# STM32__nRF24GHz.net
KiCad netlist of a schematic drawn in Altium Designer
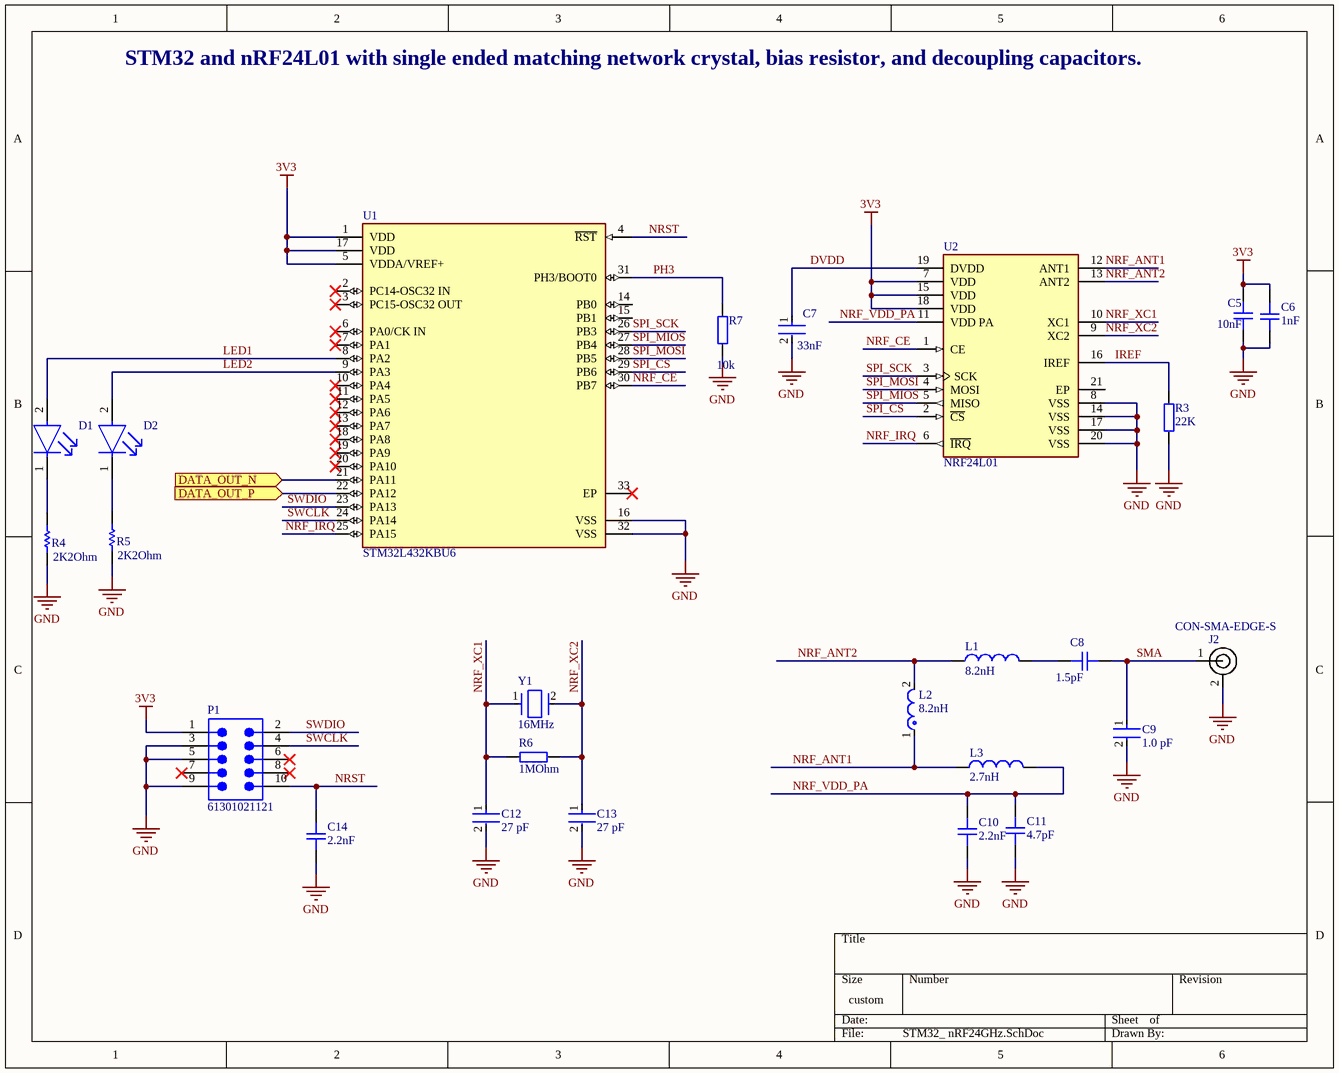
[diagram p0: STM32_ nRF24GHz.SchDoc]

(export (version "E")
  (design (tool "Eeschema 10.0.6"))
  (components
    (comp (ref "C5")
      (value "C0402")
      (footprint "CAP_0402")
      (description "Capacitor SMD 0402")
      (fields (field (name "PARAMETER 1") "10nF"))
      (libsource (lib "Schematic-Lib-PhilsLab") (part "CAP_0402"))
    )
    (comp (ref "C6")
      (value "C0402")
      (footprint "CAP_0402")
      (description "Capacitor SMD 0402")
      (fields (field (name "PARAMETER 1") "1nF"))
      (libsource (lib "Schematic-Lib-PhilsLab") (part "CAP_0402"))
    )
    (comp (ref "C7")
      (value "33nF")
      (footprint "FP-C0402-BB-MFG")
      (description "0402 C 33nF Ceramic Multilayer Capacitor; 16 V; +125degC; X7R Dielectric; +/-10%")
      (fields
        (field (name "MANUFACTURER") "Kemet")
        (field (name "MANUFACTURER PART NUMBER") "C0402C333K4RACTU")
      )
      (libsource (lib "Altium Content Vault") (part "b4654b650e69147ec39a6b967a45e02"))
    )
    (comp (ref "C8")
      (value "C0402")
      (footprint "CAP_0402")
      (description "Capacitor SMD 0402")
      (fields (field (name "PARAMETER 1") "1.5pF"))
      (libsource (lib "Schematic-Lib-PhilsLab") (part "CAP_0402"))
    )
    (comp (ref "C9")
      (value "C0402C109C5GACTU")
      (footprint "FP-C0402-BB-MFG")
      (description "CAP CER 1PF 50V NP0 0402")
      (fields
        (field (name "CAPACITANCE") "1.0 pF")
        (field (name "MANUFACTURER") "Kemet")
        (field (name "OCTOPART") "https://octopart.com/c0402c109c5gactu-kemet-9138550")
      )
      (libsource (lib "Altium Content Vault") (part "b4654b650e69147ec39a6b967a45e02"))
    )
    (comp (ref "C10")
      (value "C0402")
      (footprint "CAP_0402")
      (description "Capacitor SMD 0402")
      (fields (field (name "PARAMETER 1") "2.2nF"))
      (libsource (lib "Schematic-Lib-PhilsLab") (part "CAP_0402"))
    )
    (comp (ref "C11")
      (value "C0402")
      (footprint "CAP_0402")
      (description "Capacitor SMD 0402")
      (fields (field (name "PARAMETER 1") "4.7pF"))
      (libsource (lib "Schematic-Lib-PhilsLab") (part "CAP_0402"))
    )
    (comp (ref "C12")
      (value "27 pF")
      (footprint "FP-C0402-BB-MFG")
      (description "CAP CER 27PF 50V C0G/NP0 0402")
      (fields (field (name "MANUFACTURER") "Kemet") (field (name "TOLERANCE") "0.05"))
      (libsource (lib "Altium Content Vault") (part "b4654b650e69147ec39a6b967a45e02"))
    )
    (comp (ref "C13")
      (value "27 pF")
      (footprint "FP-C0402-BB-MFG")
      (description "CAP CER 27PF 50V C0G/NP0 0402")
      (fields (field (name "MANUFACTURER") "Kemet") (field (name "TOLERANCE") "0.05"))
      (libsource (lib "Altium Content Vault") (part "b4654b650e69147ec39a6b967a45e02"))
    )
    (comp (ref "C14")
      (value "C0402")
      (footprint "CAP_0402")
      (description "Capacitor SMD 0402")
      (fields (field (name "PARAMETER 1") "2.2nF"))
      (libsource (lib "Schematic-Lib-PhilsLab") (part "CAP_0402"))
    )
    (comp (ref "D1")
      (value "LTST-C190GKT")
      (footprint "FP-LTST-C190GKT-MFG")
      (description "LED GREEN CLEAR CHIP SMD")
      (fields (field (name "VOLTAGE") "2V"))
      (libsource (lib "Altium Content Vault") (part "8706943c75ba83719d021d2fdc84c58"))
    )
    (comp (ref "D2")
      (value "LTST-C190GKT")
      (footprint "FP-LTST-C190GKT-MFG")
      (description "LED GREEN CLEAR CHIP SMD")
      (fields (field (name "VOLTAGE") "2V"))
      (libsource (lib "Altium Content Vault") (part "8706943c75ba83719d021d2fdc84c58"))
    )
    (comp (ref "J2")
      (value "CON-SMA-EDGE-S")
      (footprint "CON-SMA-EDGE-S")
      (description "RF Connector SMA Female 50 Ohms 18 GHz PCB Edge Mount")
      (fields (field (name "MANUFACTURER") "RF Solutions"))
      (libsource (lib "Schematic-Lib-PhilsLab") (part "CON-SMA-EDGE-S"))
    )
    (comp (ref "L1")
      (value "744901082")
      (footprint "WE-TCI_0402")
      (description "744901082 Fixed Ind 8.2NH 220MA 1.1 Ohm SMD")
      (fields (field (name "INDUCTANCE") "8.2nH") (field (name "TOLERANCE") "2%"))
      (libsource (lib "Altium Content Vault") (part "Inductor - 1"))
    )
    (comp (ref "L2")
      (value "LQG15HN8N2J02D")
      (footprint "FP-LQG15HH_02-MFG")
      (description "Multilayer type RF Inductor 8.2nH ±5% 0.25Ω 500mA 0402")
      (fields (field (name "INDUCTANCE") "8.2nH") (field (name "TOLERANCE") "5%"))
      (libsource (lib "Altium Content Vault") (part "4cc4b267dca4c8e51f7102f422741d8"))
    )
    (comp (ref "L3")
      (value "744901027")
      (footprint "WE-TCI_0402")
      (description "744901027 Fixed Ind 2.7NH 440MA 300MOHM Sm")
      (fields (field (name "INDUCTANCE") "2.7nH"))
      (libsource (lib "Altium Content Vault") (part "Inductor - 1"))
    )
    (comp (ref "P1")
      (value "61301021121")
      (footprint "61301021121")
      (libsource (lib "Altium Content Vault") (part "Header_Male_2R_10P"))
    )
    (comp (ref "R3")
      (value "22K")
      (footprint "RES_0402")
      (description "Resistor SMD 0402")
      (libsource (lib "Schematic-Lib-PhilsLab") (part "RES_0402"))
    )
    (comp (ref "R4")
      (value "CRCW040242K2FKED")
      (footprint "RESC1005X40X25LL05T05")
      (fields (field (name "MANUFACTURER") "Vishay Dale") (field (name "PARAMETER 1") "2K2Ohm"))
      (libsource (lib "Altium Content Vault") (part "RES"))
    )
    (comp (ref "R5")
      (value "CRCW040242K2FKED")
      (footprint "RESC1005X40X25LL05T05")
      (fields (field (name "MANUFACTURER") "Vishay Dale") (field (name "PARAMETER 1") "2K2Ohm"))
      (libsource (lib "Altium Content Vault") (part "RES"))
    )
    (comp (ref "R6")
      (value "1MOhm")
      (footprint "RES_0402")
      (description "Resistor SMD 0402")
      (libsource (lib "Schematic-Lib-PhilsLab") (part "RES_0402"))
    )
    (comp (ref "R7")
      (value "10k")
      (footprint "RES_0402")
      (description "Resistor SMD 0402")
      (fields (field (name "RESISTANCE") "10k"))
      (libsource (lib "Schematic-Lib-PhilsLab") (part "RES_0402"))
    )
    (comp (ref "U1")
      (value "STM32L432KBU6")
      (footprint "FP-UFQFPN32-A0B8-MFG")
      (description "IC MCU 32BIT 128KB FLASH 32QFPN")
      (fields
        (field (name "MANUFACTURER") "STMicroelectronics")
        (field (name "OCTOPART") "https://octopart.com/stm32l432kbu6-stmicroelectronics-74568735")
      )
      (libsource (lib "Altium Content Vault") (part "2d0dd149e1b71adbded20be99a489b5"))
    )
    (comp (ref "U2")
      (value "NRF24L01")
      (footprint "FP-NRF24L01-IPC_C")
      (description "IC RF TXRX ISM>1GHZ 20VFQFN")
      (libsource (lib "Altium Content Vault") (part "c1991f80fab2a73cc9c289ab500ff3d"))
    )
    (comp (ref "Y1")
      (value "ABM3-16.000MHZ-D2Y-T")
      (footprint "FP-ABM3-MFG")
      (description "Crystal 16MHz ±20ppm 18pF SMD-2 5mm x 3.2mm")
      (fields (field (name "TOLERANCE") "20ppm") (field (name "FREQUENCY") "16MHz"))
      (libsource (lib "Altium Content Vault") (part "c23a69dc6c9e2f18f2079038eb95dd1"))
    )
  )
  (nets
    (net (code "1") (name "/DATA_OUT_N") (class "Default")
      (node (ref "U1") (pin "21") (pinfunction "PA11_21") (pintype "bidirectional"))
    )
    (net (code "2") (name "/DATA_OUT_P") (class "Default")
      (node (ref "U1") (pin "22") (pinfunction "PA12_22") (pintype "bidirectional"))
    )
    (net (code "3") (name "/DVDD") (class "Default")
      (node (ref "C7") (pin "1") (pinfunction "1_1") (pintype "passive"))
      (node (ref "U2") (pin "19") (pinfunction "DVDD_19") (pintype "power_in"))
    )
    (net (code "4") (name "/IREF") (class "Default")
      (node (ref "R3") (pin "2") (pinfunction "2_2") (pintype "passive"))
      (node (ref "U2") (pin "16") (pinfunction "IREF_16") (pintype "passive"))
    )
    (net (code "5") (name "/LED1") (class "Default")
      (node (ref "D1") (pin "2") (pinfunction "A_2") (pintype "passive"))
      (node (ref "U1") (pin "8") (pinfunction "PA2_8") (pintype "bidirectional"))
    )
    (net (code "6") (name "/LED2") (class "Default")
      (node (ref "D2") (pin "2") (pinfunction "A_2") (pintype "passive"))
      (node (ref "U1") (pin "9") (pinfunction "PA3_9") (pintype "bidirectional"))
    )
    (net (code "7") (name "/NRF_ANT1") (class "Default")
      (node (ref "L2") (pin "1") (pinfunction "1_1") (pintype "passive"))
      (node (ref "L3") (pin "1") (pinfunction "1_1") (pintype "passive"))
      (node (ref "U2") (pin "12") (pinfunction "ANT1_12") (pintype "passive"))
    )
    (net (code "8") (name "/NRF_ANT2") (class "Default")
      (node (ref "L1") (pin "1") (pinfunction "1_1") (pintype "passive"))
      (node (ref "L2") (pin "2") (pinfunction "2_2") (pintype "passive"))
      (node (ref "U2") (pin "13") (pinfunction "ANT2_13") (pintype "passive"))
    )
    (net (code "9") (name "/NRF_CE") (class "Default")
      (node (ref "U1") (pin "30") (pinfunction "PB7_30") (pintype "bidirectional"))
      (node (ref "U2") (pin "1") (pinfunction "CE_1") (pintype "input"))
    )
    (net (code "10") (name "/NRF_IRQ") (class "Default")
      (node (ref "U1") (pin "25") (pinfunction "PA15_25") (pintype "bidirectional"))
      (node (ref "U2") (pin "6") (pinfunction "~{IRQ}_6") (pintype "output"))
    )
    (net (code "11") (name "/NRF_VDD_PA") (class "Default")
      (node (ref "C10") (pin "2") (pinfunction "2_2") (pintype "passive"))
      (node (ref "C11") (pin "2") (pinfunction "2_2") (pintype "passive"))
      (node (ref "L3") (pin "2") (pinfunction "2_2") (pintype "passive"))
      (node (ref "U2") (pin "11") (pinfunction "VDD_PA_11") (pintype "power_in"))
    )
    (net (code "12") (name "/NRF_XC1") (class "Default")
      (node (ref "C12") (pin "1") (pinfunction "1_1") (pintype "passive"))
      (node (ref "R6") (pin "2") (pinfunction "2_2") (pintype "passive"))
      (node (ref "U2") (pin "10") (pinfunction "XC1_10") (pintype "passive"))
      (node (ref "Y1") (pin "1") (pinfunction "1_1") (pintype "passive"))
    )
    (net (code "13") (name "/NRF_XC2") (class "Default")
      (node (ref "C13") (pin "1") (pinfunction "1_1") (pintype "passive"))
      (node (ref "R6") (pin "1") (pinfunction "1_1") (pintype "passive"))
      (node (ref "U2") (pin "9") (pinfunction "XC2_9") (pintype "passive"))
      (node (ref "Y1") (pin "2") (pinfunction "2_2") (pintype "passive"))
    )
    (net (code "14") (name "/NRST") (class "Default")
      (node (ref "C14") (pin "2") (pinfunction "2_2") (pintype "passive"))
      (node (ref "P1") (pin "10") (pinfunction "10_10") (pintype "passive"))
      (node (ref "U1") (pin "4") (pinfunction "~{RST}_4") (pintype "input"))
    )
    (net (code "15") (name "/PH3") (class "Default")
      (node (ref "R7") (pin "1") (pinfunction "1_1") (pintype "passive"))
      (node (ref "U1") (pin "31") (pinfunction "PH3/BOOT0_31") (pintype "bidirectional"))
    )
    (net (code "16") (name "/SMA") (class "Default")
      (node (ref "C8") (pin "2") (pinfunction "2_2") (pintype "passive"))
      (node (ref "C9") (pin "1") (pinfunction "1_1") (pintype "passive"))
      (node (ref "J2") (pin "1") (pinfunction "1_1") (pintype "passive"))
    )
    (net (code "17") (name "/SPI_CS") (class "Default")
      (node (ref "U1") (pin "29") (pinfunction "PB6_29") (pintype "bidirectional"))
      (node (ref "U2") (pin "2") (pinfunction "~{CS}_2") (pintype "input"))
    )
    (net (code "18") (name "/SPI_MIOS") (class "Default")
      (node (ref "U1") (pin "27") (pinfunction "PB4_27") (pintype "bidirectional"))
      (node (ref "U2") (pin "5") (pinfunction "MISO_5") (pintype "output"))
    )
    (net (code "19") (name "/SPI_MOSI") (class "Default")
      (node (ref "U1") (pin "28") (pinfunction "PB5_28") (pintype "bidirectional"))
      (node (ref "U2") (pin "4") (pinfunction "MOSI_4") (pintype "input"))
    )
    (net (code "20") (name "/SPI_SCK") (class "Default")
      (node (ref "U1") (pin "26") (pinfunction "PB3_26") (pintype "bidirectional"))
      (node (ref "U2") (pin "3") (pinfunction "SCK_3") (pintype "input"))
    )
    (net (code "21") (name "/SWCLK") (class "Default")
      (node (ref "P1") (pin "4") (pinfunction "4_4") (pintype "passive"))
      (node (ref "U1") (pin "24") (pinfunction "PA14_24") (pintype "bidirectional"))
    )
    (net (code "22") (name "/SWDIO") (class "Default")
      (node (ref "P1") (pin "2") (pinfunction "2_2") (pintype "passive"))
      (node (ref "U1") (pin "23") (pinfunction "PA13_23") (pintype "bidirectional"))
    )
    (net (code "23") (name "3V3") (class "Default")
      (node (ref "C5") (pin "2") (pinfunction "2_2") (pintype "passive"))
      (node (ref "C6") (pin "2") (pinfunction "2_2") (pintype "passive"))
      (node (ref "P1") (pin "1") (pinfunction "1_1") (pintype "passive"))
      (node (ref "U1") (pin "1") (pinfunction "VDD_1") (pintype "power_in"))
      (node (ref "U1") (pin "17") (pinfunction "VDD_17") (pintype "power_in"))
      (node (ref "U1") (pin "5") (pinfunction "VDDA/VREF+_5") (pintype "power_in"))
      (node (ref "U2") (pin "15") (pinfunction "VDD_15") (pintype "power_in"))
      (node (ref "U2") (pin "18") (pinfunction "VDD_18") (pintype "power_in"))
      (node (ref "U2") (pin "7") (pinfunction "VDD_7") (pintype "power_in"))
    )
    (net (code "24") (name "GND") (class "Default")
      (node (ref "C10") (pin "1") (pinfunction "1_1") (pintype "passive"))
      (node (ref "C11") (pin "1") (pinfunction "1_1") (pintype "passive"))
      (node (ref "C12") (pin "2") (pinfunction "2_2") (pintype "passive"))
      (node (ref "C13") (pin "2") (pinfunction "2_2") (pintype "passive"))
      (node (ref "C14") (pin "1") (pinfunction "1_1") (pintype "passive"))
      (node (ref "C5") (pin "1") (pinfunction "1_1") (pintype "passive"))
      (node (ref "C6") (pin "1") (pinfunction "1_1") (pintype "passive"))
      (node (ref "C7") (pin "2") (pinfunction "2_2") (pintype "passive"))
      (node (ref "C9") (pin "2") (pinfunction "2_2") (pintype "passive"))
      (node (ref "J2") (pin "2") (pinfunction "2_2") (pintype "passive"))
      (node (ref "P1") (pin "3") (pinfunction "3_3") (pintype "passive"))
      (node (ref "P1") (pin "5") (pinfunction "5_5") (pintype "passive"))
      (node (ref "P1") (pin "9") (pinfunction "9_9") (pintype "passive"))
      (node (ref "R3") (pin "1") (pinfunction "1_1") (pintype "passive"))
      (node (ref "R4") (pin "1") (pinfunction "1_1") (pintype "passive"))
      (node (ref "R5") (pin "1") (pinfunction "1_1") (pintype "passive"))
      (node (ref "R7") (pin "2") (pinfunction "2_2") (pintype "passive"))
      (node (ref "U1") (pin "16") (pinfunction "VSS_16") (pintype "power_in"))
      (node (ref "U1") (pin "32") (pinfunction "VSS_32") (pintype "power_in"))
      (node (ref "U2") (pin "14") (pinfunction "VSS_14") (pintype "power_in"))
      (node (ref "U2") (pin "17") (pinfunction "VSS_17") (pintype "power_in"))
      (node (ref "U2") (pin "20") (pinfunction "VSS_20") (pintype "power_in"))
      (node (ref "U2") (pin "8") (pinfunction "VSS_8") (pintype "power_in"))
    )
    (net (code "25") (name "Net-(C8-Pad1)") (class "Default")
      (node (ref "C8") (pin "1") (pinfunction "1_1") (pintype "passive"))
      (node (ref "L1") (pin "2") (pinfunction "2_2") (pintype "passive"))
    )
    (net (code "26") (name "Net-(D1-C)") (class "Default")
      (node (ref "D1") (pin "1") (pinfunction "C_1") (pintype "passive"))
      (node (ref "R4") (pin "2") (pinfunction "2_2") (pintype "passive"))
    )
    (net (code "27") (name "Net-(D2-C)") (class "Default")
      (node (ref "D2") (pin "1") (pinfunction "C_1") (pintype "passive"))
      (node (ref "R5") (pin "2") (pinfunction "2_2") (pintype "passive"))
    )
    (net (code "28") (name "unconnected-(P1-Pad6)") (class "Default")
      (node (ref "P1") (pin "6") (pinfunction "6_6") (pintype "passive+no_connect"))
    )
    (net (code "29") (name "unconnected-(P1-Pad7)") (class "Default")
      (node (ref "P1") (pin "7") (pinfunction "7_7") (pintype "passive+no_connect"))
    )
    (net (code "30") (name "unconnected-(P1-Pad8)") (class "Default")
      (node (ref "P1") (pin "8") (pinfunction "8_8") (pintype "passive+no_connect"))
    )
    (net (code "31") (name "unconnected-(U1-EP-Pad33)") (class "Default")
      (node (ref "U1") (pin "33") (pinfunction "EP_33") (pintype "power_in+no_connect"))
    )
    (net (code "32") (name "unconnected-(U1-PA0{slash}CK_IN-Pad6)") (class "Default")
      (node (ref "U1") (pin "6") (pinfunction "PA0/CK_IN_6") (pintype "bidirectional+no_connect"))
    )
    (net (code "33") (name "unconnected-(U1-PA1-Pad7)") (class "Default")
      (node (ref "U1") (pin "7") (pinfunction "PA1_7") (pintype "bidirectional+no_connect"))
    )
    (net (code "34") (name "unconnected-(U1-PA4-Pad10)") (class "Default")
      (node (ref "U1") (pin "10") (pinfunction "PA4_10") (pintype "bidirectional+no_connect"))
    )
    (net (code "35") (name "unconnected-(U1-PA5-Pad11)") (class "Default")
      (node (ref "U1") (pin "11") (pinfunction "PA5_11") (pintype "bidirectional+no_connect"))
    )
    (net (code "36") (name "unconnected-(U1-PA6-Pad12)") (class "Default")
      (node (ref "U1") (pin "12") (pinfunction "PA6_12") (pintype "bidirectional+no_connect"))
    )
    (net (code "37") (name "unconnected-(U1-PA7-Pad13)") (class "Default")
      (node (ref "U1") (pin "13") (pinfunction "PA7_13") (pintype "bidirectional+no_connect"))
    )
    (net (code "38") (name "unconnected-(U1-PA8-Pad18)") (class "Default")
      (node (ref "U1") (pin "18") (pinfunction "PA8_18") (pintype "bidirectional+no_connect"))
    )
    (net (code "39") (name "unconnected-(U1-PA9-Pad19)") (class "Default")
      (node (ref "U1") (pin "19") (pinfunction "PA9_19") (pintype "bidirectional+no_connect"))
    )
    (net (code "40") (name "unconnected-(U1-PA10-Pad20)") (class "Default")
      (node (ref "U1") (pin "20") (pinfunction "PA10_20") (pintype "bidirectional+no_connect"))
    )
    (net (code "41") (name "unconnected-(U1-PB0-Pad14)") (class "Default")
      (node (ref "U1") (pin "14") (pinfunction "PB0_14") (pintype "bidirectional"))
    )
    (net (code "42") (name "unconnected-(U1-PB1-Pad15)") (class "Default")
      (node (ref "U1") (pin "15") (pinfunction "PB1_15") (pintype "bidirectional"))
    )
    (net (code "43") (name "unconnected-(U1-PC14-OSC32_IN-Pad2)") (class "Default")
      (node (ref "U1") (pin "2") (pinfunction "PC14-OSC32_IN_2") (pintype "bidirectional+no_connect"))
    )
    (net (code "44") (name "unconnected-(U1-PC15-OSC32_OUT-Pad3)") (class "Default")
      (node (ref "U1") (pin "3") (pinfunction "PC15-OSC32_OUT_3") (pintype "bidirectional+no_connect"))
    )
    (net (code "45") (name "unconnected-(U2-EP-Pad21)") (class "Default")
      (node (ref "U2") (pin "21") (pinfunction "EP_21") (pintype "power_in"))
    )
  )
)
